# alpha.net
KiCad netlist of a schematic drawn in EAGLE
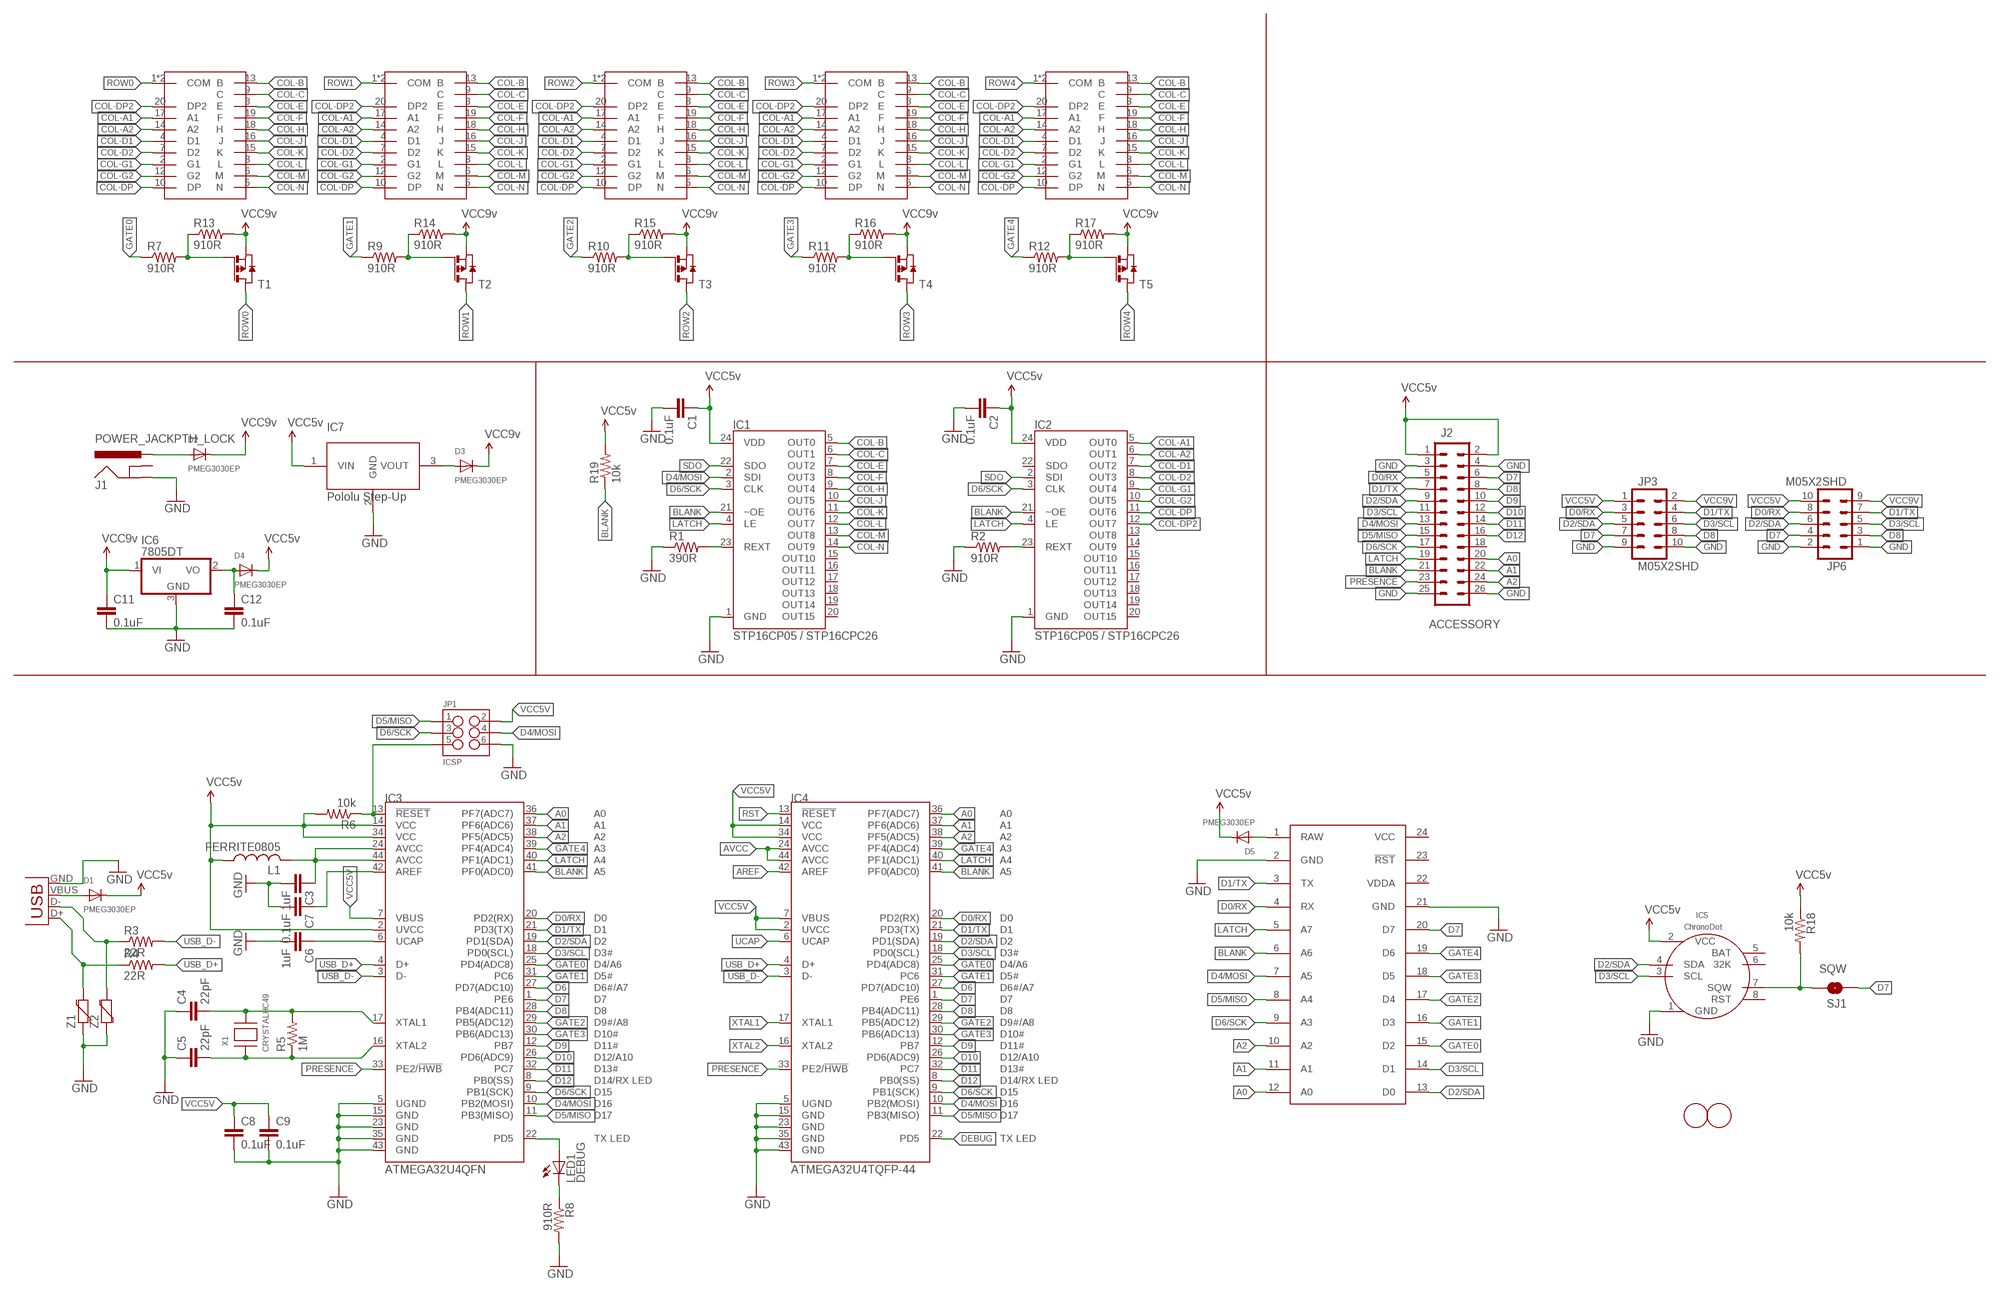
[diagram p0: schematic, sheet 1]

(export (version "E")
  (design (tool "Eeschema 10.0.6"))
  (components
    (comp (ref "C1")
      (value "0.1uF")
      (footprint "eagle-import:0805")
      (fields (field (name "PARTNO") "C0805C104K5RACTU"))
      (libsource (lib "eagle-import") (part "CAP0805"))
    )
    (comp (ref "C2")
      (value "0.1uF")
      (footprint "eagle-import:0805")
      (fields (field (name "PARTNO") "C0805C104K5RACTU"))
      (libsource (lib "eagle-import") (part "CAP0805"))
    )
    (comp (ref "C3")
      (value "1uF")
      (footprint "eagle-import:0805")
      (fields (field (name "PARTNO") "CL21B105KBFNNNE"))
      (libsource (lib "eagle-import") (part "CAP0805"))
    )
    (comp (ref "C4")
      (value "22pF")
      (footprint "eagle-import:0805")
      (fields (field (name "PARTNO") "C0805C220J5GACTU"))
      (libsource (lib "eagle-import") (part "CAP0805"))
    )
    (comp (ref "C5")
      (value "22pF")
      (footprint "eagle-import:0805")
      (fields (field (name "PARTNO") "C0805C220J5GACTU"))
      (libsource (lib "eagle-import") (part "CAP0805"))
    )
    (comp (ref "C6")
      (value "1uF")
      (footprint "eagle-import:0805")
      (fields (field (name "PARTNO") "CL21B105KBFNNNE"))
      (libsource (lib "eagle-import") (part "CAP0805"))
    )
    (comp (ref "C7")
      (value "0.1uF")
      (footprint "eagle-import:0805")
      (fields (field (name "PARTNO") "C0805C104K5RACTU"))
      (libsource (lib "eagle-import") (part "CAP0805"))
    )
    (comp (ref "C8")
      (value "0.1uF")
      (footprint "eagle-import:0805")
      (fields (field (name "PARTNO") "C0805C104K5RACTU"))
      (libsource (lib "eagle-import") (part "CAP0805"))
    )
    (comp (ref "C9")
      (value "0.1uF")
      (footprint "eagle-import:0805")
      (fields (field (name "PARTNO") "C0805C104K5RACTU"))
      (libsource (lib "eagle-import") (part "CAP0805"))
    )
    (comp (ref "C11")
      (value "0.1uF")
      (footprint "eagle-import:0805")
      (fields (field (name "PARTNO") "C0805C104K5RACTU"))
      (libsource (lib "eagle-import") (part "CAP0805"))
    )
    (comp (ref "C12")
      (value "0.1uF")
      (footprint "eagle-import:0805")
      (fields (field (name "PARTNO") "C0805C104K5RACTU"))
      (libsource (lib "eagle-import") (part "CAP0805"))
    )
    (comp (ref "CORE")
      (value "Spark Core")
      (footprint "eagle-import:SPARK_CORE")
      (libsource (lib "eagle-import") (part "SPARK_CORECORE"))
    )
    (comp (ref "D1")
      (value "PMEG3030EP")
      (footprint "eagle-import:SOD-128")
      (fields (field (name "PARTNO") "PMEG3030EP-115"))
      (libsource (lib "eagle-import") (part "DIODESOD-128"))
    )
    (comp (ref "D2")
      (value "PMEG3030EP")
      (footprint "eagle-import:SOD-128")
      (fields (field (name "PARTNO") "PMEG3030EP-115"))
      (libsource (lib "eagle-import") (part "DIODESOD-128"))
    )
    (comp (ref "D3")
      (value "PMEG3030EP")
      (footprint "eagle-import:SOD-128")
      (fields (field (name "PARTNO") "PMEG3030EP-115"))
      (libsource (lib "eagle-import") (part "DIODESOD-128"))
    )
    (comp (ref "D4")
      (value "PMEG3030EP")
      (footprint "eagle-import:SOD-128")
      (fields (field (name "PARTNO") "PMEG3030EP-115"))
      (libsource (lib "eagle-import") (part "DIODESOD-128"))
    )
    (comp (ref "D5")
      (value "PMEG3030EP")
      (footprint "eagle-import:SOD-128")
      (fields (field (name "PARTNO") "PMEG3030EP-115"))
      (libsource (lib "eagle-import") (part "DIODESOD-128"))
    )
    (comp (ref "IC1")
      (value "STP16CP05 / STP16CPC26")
      (footprint "eagle-import:SO-24DW")
      (fields (field (name "PARTNO") "STP16CPC26MTR"))
      (libsource (lib "eagle-import") (part "STP16CP05"))
    )
    (comp (ref "IC2")
      (value "STP16CP05 / STP16CPC26")
      (footprint "eagle-import:SO-24DW")
      (fields (field (name "PARTNO") "STP16CPC26MTR"))
      (libsource (lib "eagle-import") (part "STP16CP05"))
    )
    (comp (ref "IC3")
      (value "ATMEGA32U4QFN")
      (footprint "eagle-import:QFN-44")
      (fields (field (name "PARTNO") "ATMEGA32U4-MUR"))
      (libsource (lib "eagle-import") (part "ATMEGA32U4QFN"))
    )
    (comp (ref "IC4")
      (value "ATMEGA32U4TQFP-44")
      (footprint "eagle-import:TQFP44")
      (fields (field (name "PARTNO") "ATMEGA32U4-AU"))
      (libsource (lib "eagle-import") (part "ATMEGA32U4TQFP-44"))
    )
    (comp (ref "IC5")
      (value "CHRONODOT")
      (footprint "eagle-import:CHRONODOT")
      (libsource (lib "eagle-import") (part "CHRONODOT"))
    )
    (comp (ref "IC6")
      (value "7805DT")
      (footprint "eagle-import:TO252")
      (libsource (lib "eagle-import") (part "78DT05"))
    )
    (comp (ref "IC7")
      (value "Pololu Step-Up")
      (footprint "eagle-import:1X03_LOCK")
      (libsource (lib "eagle-import") (part "POLOLU_REG"))
    )
    (comp (ref "J1")
      (value "POWER_JACKPTH_LOCK")
      (footprint "eagle-import:POWER_JACK_PTH_LOCK")
      (fields (field (name "PARTNO") "PJ-202A"))
      (libsource (lib "eagle-import") (part "POWER_JACKPTH_LOCK"))
    )
    (comp (ref "J2")
      (value "ACCESSORY")
      (footprint "eagle-import:2X13")
      (fields (field (name "PARTNO") "SFH11-PBPC-D13-ST-BK"))
      (libsource (lib "eagle-import") (part "HEADER-M26"))
    )
    (comp (ref "JP1")
      (value "ICSP")
      (footprint "eagle-import:2X3-NS")
      (fields (field (name "PARTNO") "M20-9980346"))
      (libsource (lib "eagle-import") (part "M03X2NO_SILK"))
    )
    (comp (ref "JP2")
      (value "USBSMD")
      (footprint "eagle-import:USB-MINIB")
      (fields (field (name "PARTNO") "690-005-299-043"))
      (libsource (lib "eagle-import") (part "USBSMD"))
    )
    (comp (ref "JP3")
      (value "M05X2SHD")
      (footprint "eagle-import:2X5-SHROUDED")
      (fields (field (name "PARTNO") "302-S101"))
      (libsource (lib "eagle-import") (part "M05X2SHD"))
    )
    (comp (ref "JP6")
      (value "M05X2SHD")
      (footprint "eagle-import:2X5-SHROUDED")
      (fields (field (name "PARTNO") "302-S101"))
      (libsource (lib "eagle-import") (part "M05X2SHD"))
    )
    (comp (ref "L1")
      (value "FERRITE0805")
      (footprint "eagle-import:0805")
      (fields (field (name "PARTNO") "CIM21J601NE"))
      (libsource (lib "eagle-import") (part "FERRITE0805"))
    )
    (comp (ref "LED1")
      (value "DEBUG")
      (footprint "eagle-import:CHIP-LED0805")
      (fields (field (name "PARTNO") "LG R971-KN-1"))
      (libsource (lib "eagle-import") (part "LEDCHIP-LED0805"))
    )
    (comp (ref "R1")
      (value "390R")
      (footprint "eagle-import:0805")
      (fields (field (name "PARTNO") "RC0805FR-07390RL"))
      (libsource (lib "eagle-import") (part "RESISTOR0805-RES"))
    )
    (comp (ref "R2")
      (value "910R")
      (footprint "eagle-import:0805")
      (fields (field (name "PARTNO") "MCR10ERTF9100"))
      (libsource (lib "eagle-import") (part "RESISTOR0805-RES"))
    )
    (comp (ref "R3")
      (value "22R")
      (footprint "eagle-import:0805")
      (fields (field (name "PARTNO") "RC0805FR-0722RL"))
      (libsource (lib "eagle-import") (part "RESISTOR0805-RES"))
    )
    (comp (ref "R4")
      (value "22R")
      (footprint "eagle-import:0805")
      (fields (field (name "PARTNO") "RC0805FR-0722RL"))
      (libsource (lib "eagle-import") (part "RESISTOR0805-RES"))
    )
    (comp (ref "R5")
      (value "1M")
      (footprint "eagle-import:0805")
      (fields (field (name "PARTNO") "RC0805FR-071ML"))
      (libsource (lib "eagle-import") (part "RESISTOR0805-RES"))
    )
    (comp (ref "R6")
      (value "10k")
      (footprint "eagle-import:0805")
      (fields (field (name "PARTNO") "RC0805JR-0710KL"))
      (libsource (lib "eagle-import") (part "RESISTOR0805-RES"))
    )
    (comp (ref "R7")
      (value "910R")
      (footprint "eagle-import:0805")
      (fields (field (name "PARTNO") "MCR10ERTF9100"))
      (libsource (lib "eagle-import") (part "RESISTOR0805-RES"))
    )
    (comp (ref "R8")
      (value "910R")
      (footprint "eagle-import:0805")
      (fields (field (name "PARTNO") "MCR10ERTF9100"))
      (libsource (lib "eagle-import") (part "RESISTOR0805-RES"))
    )
    (comp (ref "R9")
      (value "910R")
      (footprint "eagle-import:0805")
      (fields (field (name "PARTNO") "MCR10ERTF9100"))
      (libsource (lib "eagle-import") (part "RESISTOR0805-RES"))
    )
    (comp (ref "R10")
      (value "910R")
      (footprint "eagle-import:0805")
      (fields (field (name "PARTNO") "MCR10ERTF9100"))
      (libsource (lib "eagle-import") (part "RESISTOR0805-RES"))
    )
    (comp (ref "R11")
      (value "910R")
      (footprint "eagle-import:0805")
      (fields (field (name "PARTNO") "MCR10ERTF9100"))
      (libsource (lib "eagle-import") (part "RESISTOR0805-RES"))
    )
    (comp (ref "R12")
      (value "910R")
      (footprint "eagle-import:0805")
      (fields (field (name "PARTNO") "MCR10ERTF9100"))
      (libsource (lib "eagle-import") (part "RESISTOR0805-RES"))
    )
    (comp (ref "R13")
      (value "910R")
      (footprint "eagle-import:0805")
      (fields (field (name "PARTNO") "MCR10ERTF9100"))
      (libsource (lib "eagle-import") (part "RESISTOR0805-RES"))
    )
    (comp (ref "R14")
      (value "910R")
      (footprint "eagle-import:0805")
      (fields (field (name "PARTNO") "MCR10ERTF9100"))
      (libsource (lib "eagle-import") (part "RESISTOR0805-RES"))
    )
    (comp (ref "R15")
      (value "910R")
      (footprint "eagle-import:0805")
      (fields (field (name "PARTNO") "MCR10ERTF9100"))
      (libsource (lib "eagle-import") (part "RESISTOR0805-RES"))
    )
    (comp (ref "R16")
      (value "910R")
      (footprint "eagle-import:0805")
      (fields (field (name "PARTNO") "MCR10ERTF9100"))
      (libsource (lib "eagle-import") (part "RESISTOR0805-RES"))
    )
    (comp (ref "R17")
      (value "910R")
      (footprint "eagle-import:0805")
      (fields (field (name "PARTNO") "MCR10ERTF9100"))
      (libsource (lib "eagle-import") (part "RESISTOR0805-RES"))
    )
    (comp (ref "R18")
      (value "10k")
      (footprint "eagle-import:0805")
      (fields (field (name "PARTNO") "RC0805JR-0710KL"))
      (libsource (lib "eagle-import") (part "RESISTOR0805-RES"))
    )
    (comp (ref "R19")
      (value "10k")
      (footprint "eagle-import:0805")
      (libsource (lib "eagle-import") (part "RESISTOR0805-RES"))
    )
    (comp (ref "SEG1")
      (value "BL-S230X-12")
      (footprint "eagle-import:BL-S230X-12")
      (libsource (lib "eagle-import") (part "BL-S230X-12"))
    )
    (comp (ref "SEG2")
      (value "BL-S230X-12")
      (footprint "eagle-import:BL-S230X-12")
      (libsource (lib "eagle-import") (part "BL-S230X-12"))
    )
    (comp (ref "SEG3")
      (value "BL-S230X-12")
      (footprint "eagle-import:BL-S230X-12")
      (libsource (lib "eagle-import") (part "BL-S230X-12"))
    )
    (comp (ref "SEG4")
      (value "BL-S230X-12")
      (footprint "eagle-import:BL-S230X-12")
      (libsource (lib "eagle-import") (part "BL-S230X-12"))
    )
    (comp (ref "SEG5")
      (value "BL-S230X-12")
      (footprint "eagle-import:BL-S230X-12")
      (libsource (lib "eagle-import") (part "BL-S230X-12"))
    )
    (comp (ref "SJ1")
      (value "SQW")
      (footprint "eagle-import:SJ_2S-NO")
      (libsource (lib "eagle-import") (part "SOLDERJUMPERNO"))
    )
    (comp (ref "T1")
      (value "PMOSSOT23")
      (footprint "eagle-import:SOT-23")
      (fields (field (name "PARTNO") "FDN352AP"))
      (libsource (lib "eagle-import") (part "PMOSSOT23"))
    )
    (comp (ref "T2")
      (value "PMOSSOT23")
      (footprint "eagle-import:SOT-23")
      (fields (field (name "PARTNO") "FDN352AP"))
      (libsource (lib "eagle-import") (part "PMOSSOT23"))
    )
    (comp (ref "T3")
      (value "PMOSSOT23")
      (footprint "eagle-import:SOT-23")
      (fields (field (name "PARTNO") "FDN352AP"))
      (libsource (lib "eagle-import") (part "PMOSSOT23"))
    )
    (comp (ref "T4")
      (value "PMOSSOT23")
      (footprint "eagle-import:SOT-23")
      (fields (field (name "PARTNO") "FDN352AP"))
      (libsource (lib "eagle-import") (part "PMOSSOT23"))
    )
    (comp (ref "T5")
      (value "PMOSSOT23")
      (footprint "eagle-import:SOT-23")
      (fields (field (name "PARTNO") "FDN352AP"))
      (libsource (lib "eagle-import") (part "PMOSSOT23"))
    )
    (comp (ref "U$1")
      (value "FIDUCIAL")
      (footprint "eagle-import:FIDUCIAL_1MM")
      (libsource (lib "eagle-import") (part "FIDUCIAL"))
    )
    (comp (ref "U$2")
      (value "FIDUCIAL")
      (footprint "eagle-import:FIDUCIAL_1MM")
      (libsource (lib "eagle-import") (part "FIDUCIAL"))
    )
    (comp (ref "X1")
      (value "CRYSTALHC49")
      (footprint "eagle-import:HC49")
      (fields (field (name "PARTNO") "9C-16.000MAAJ-T"))
      (libsource (lib "eagle-import") (part "CRYSTALHC49"))
    )
    (comp (ref "Z1")
      (value "VARISTOR-0603")
      (footprint "eagle-import:0603-RES")
      (fields (field (name "PARTNO") "CG0603MLC-05E"))
      (libsource (lib "eagle-import") (part "VARISTOR-0603"))
    )
    (comp (ref "Z2")
      (value "VARISTOR-0603")
      (footprint "eagle-import:0603-RES")
      (fields (field (name "PARTNO") "CG0603MLC-05E"))
      (libsource (lib "eagle-import") (part "VARISTOR-0603"))
    )
  )
  (nets
    (net (code "1") (name "/VCC") (class "Default")
      (node (ref "CORE") (pin "24") (pinfunction "VCC_24") (pintype "power_in"))
    )
    (net (code "2") (name "/VDDA") (class "Default")
      (node (ref "CORE") (pin "22") (pinfunction "VDDA_22") (pintype "power_in"))
    )
    (net (code "3") (name "A0") (class "Default")
      (node (ref "CORE") (pin "12") (pinfunction "A0_12") (pintype "bidirectional"))
      (node (ref "IC3") (pin "36") (pinfunction "PF7(ADC7)_36") (pintype "bidirectional"))
      (node (ref "IC4") (pin "36") (pinfunction "PF7(ADC7)_36") (pintype "bidirectional"))
      (node (ref "J2") (pin "20") (pinfunction "20_20") (pintype "passive"))
    )
    (net (code "4") (name "A1") (class "Default")
      (node (ref "CORE") (pin "11") (pinfunction "A1_11") (pintype "bidirectional"))
      (node (ref "IC3") (pin "37") (pinfunction "PF6(ADC6)_37") (pintype "bidirectional"))
      (node (ref "IC4") (pin "37") (pinfunction "PF6(ADC6)_37") (pintype "bidirectional"))
      (node (ref "J2") (pin "22") (pinfunction "22_22") (pintype "passive"))
    )
    (net (code "5") (name "A2") (class "Default")
      (node (ref "CORE") (pin "10") (pinfunction "A2_10") (pintype "bidirectional"))
      (node (ref "IC3") (pin "38") (pinfunction "PF5(ADC5)_38") (pintype "bidirectional"))
      (node (ref "IC4") (pin "38") (pinfunction "PF5(ADC5)_38") (pintype "bidirectional"))
      (node (ref "J2") (pin "24") (pinfunction "24_24") (pintype "passive"))
    )
    (net (code "6") (name "AREF") (class "Default")
      (node (ref "C7") (pin "1") (pinfunction "1_1") (pintype "passive"))
      (node (ref "IC3") (pin "42") (pinfunction "AREF_42") (pintype "bidirectional"))
      (node (ref "IC4") (pin "42") (pinfunction "AREF_42") (pintype "bidirectional"))
    )
    (net (code "7") (name "AVCC") (class "Default")
      (node (ref "C3") (pin "1") (pinfunction "1_1") (pintype "passive"))
      (node (ref "IC3") (pin "24") (pinfunction "AVCC_24") (pintype "bidirectional"))
      (node (ref "IC3") (pin "44") (pinfunction "AVCC_44") (pintype "bidirectional"))
      (node (ref "IC4") (pin "24") (pinfunction "AVCC_24") (pintype "bidirectional"))
      (node (ref "IC4") (pin "44") (pinfunction "AVCC_44") (pintype "bidirectional"))
      (node (ref "L1") (pin "2") (pinfunction "2_2") (pintype "passive"))
    )
    (net (code "8") (name "BLANK") (class "Default")
      (node (ref "CORE") (pin "6") (pinfunction "A6_6") (pintype "bidirectional"))
      (node (ref "IC1") (pin "21") (pinfunction "~{OE}_21") (pintype "bidirectional"))
      (node (ref "IC2") (pin "21") (pinfunction "~{OE}_21") (pintype "bidirectional"))
      (node (ref "IC3") (pin "41") (pinfunction "PF0(ADC0)_41") (pintype "bidirectional"))
      (node (ref "IC4") (pin "41") (pinfunction "PF0(ADC0)_41") (pintype "bidirectional"))
      (node (ref "J2") (pin "21") (pinfunction "21_21") (pintype "passive"))
      (node (ref "R19") (pin "1") (pinfunction "1_1") (pintype "passive"))
    )
    (net (code "9") (name "COL-A1") (class "Default")
      (node (ref "IC2") (pin "5") (pinfunction "OUT0_5") (pintype "bidirectional"))
      (node (ref "SEG1") (pin "17") (pinfunction "A1_17") (pintype "bidirectional"))
      (node (ref "SEG2") (pin "17") (pinfunction "A1_17") (pintype "bidirectional"))
      (node (ref "SEG3") (pin "17") (pinfunction "A1_17") (pintype "bidirectional"))
      (node (ref "SEG4") (pin "17") (pinfunction "A1_17") (pintype "bidirectional"))
      (node (ref "SEG5") (pin "17") (pinfunction "A1_17") (pintype "bidirectional"))
    )
    (net (code "10") (name "COL-A2") (class "Default")
      (node (ref "IC2") (pin "6") (pinfunction "OUT1_6") (pintype "bidirectional"))
      (node (ref "SEG1") (pin "14") (pinfunction "A2_14") (pintype "bidirectional"))
      (node (ref "SEG2") (pin "14") (pinfunction "A2_14") (pintype "bidirectional"))
      (node (ref "SEG3") (pin "14") (pinfunction "A2_14") (pintype "bidirectional"))
      (node (ref "SEG4") (pin "14") (pinfunction "A2_14") (pintype "bidirectional"))
      (node (ref "SEG5") (pin "14") (pinfunction "A2_14") (pintype "bidirectional"))
    )
    (net (code "11") (name "COL-B") (class "Default")
      (node (ref "IC1") (pin "5") (pinfunction "OUT0_5") (pintype "bidirectional"))
      (node (ref "SEG1") (pin "13") (pinfunction "B_13") (pintype "bidirectional"))
      (node (ref "SEG2") (pin "13") (pinfunction "B_13") (pintype "bidirectional"))
      (node (ref "SEG3") (pin "13") (pinfunction "B_13") (pintype "bidirectional"))
      (node (ref "SEG4") (pin "13") (pinfunction "B_13") (pintype "bidirectional"))
      (node (ref "SEG5") (pin "13") (pinfunction "B_13") (pintype "bidirectional"))
    )
    (net (code "12") (name "COL-C") (class "Default")
      (node (ref "IC1") (pin "6") (pinfunction "OUT1_6") (pintype "bidirectional"))
      (node (ref "SEG1") (pin "9") (pinfunction "C_9") (pintype "bidirectional"))
      (node (ref "SEG2") (pin "9") (pinfunction "C_9") (pintype "bidirectional"))
      (node (ref "SEG3") (pin "9") (pinfunction "C_9") (pintype "bidirectional"))
      (node (ref "SEG4") (pin "9") (pinfunction "C_9") (pintype "bidirectional"))
      (node (ref "SEG5") (pin "9") (pinfunction "C_9") (pintype "bidirectional"))
    )
    (net (code "13") (name "COL-D1") (class "Default")
      (node (ref "IC2") (pin "7") (pinfunction "OUT2_7") (pintype "bidirectional"))
      (node (ref "SEG1") (pin "4") (pinfunction "D1_4") (pintype "bidirectional"))
      (node (ref "SEG2") (pin "4") (pinfunction "D1_4") (pintype "bidirectional"))
      (node (ref "SEG3") (pin "4") (pinfunction "D1_4") (pintype "bidirectional"))
      (node (ref "SEG4") (pin "4") (pinfunction "D1_4") (pintype "bidirectional"))
      (node (ref "SEG5") (pin "4") (pinfunction "D1_4") (pintype "bidirectional"))
    )
    (net (code "14") (name "COL-D2") (class "Default")
      (node (ref "IC2") (pin "8") (pinfunction "OUT3_8") (pintype "bidirectional"))
      (node (ref "SEG1") (pin "7") (pinfunction "D2_7") (pintype "bidirectional"))
      (node (ref "SEG2") (pin "7") (pinfunction "D2_7") (pintype "bidirectional"))
      (node (ref "SEG3") (pin "7") (pinfunction "D2_7") (pintype "bidirectional"))
      (node (ref "SEG4") (pin "7") (pinfunction "D2_7") (pintype "bidirectional"))
      (node (ref "SEG5") (pin "7") (pinfunction "D2_7") (pintype "bidirectional"))
    )
    (net (code "15") (name "COL-DP") (class "Default")
      (node (ref "IC2") (pin "11") (pinfunction "OUT6_11") (pintype "bidirectional"))
      (node (ref "SEG1") (pin "10") (pinfunction "DP_10") (pintype "bidirectional"))
      (node (ref "SEG2") (pin "10") (pinfunction "DP_10") (pintype "bidirectional"))
      (node (ref "SEG3") (pin "10") (pinfunction "DP_10") (pintype "bidirectional"))
      (node (ref "SEG4") (pin "10") (pinfunction "DP_10") (pintype "bidirectional"))
      (node (ref "SEG5") (pin "10") (pinfunction "DP_10") (pintype "bidirectional"))
    )
    (net (code "16") (name "COL-DP2") (class "Default")
      (node (ref "IC2") (pin "12") (pinfunction "OUT7_12") (pintype "bidirectional"))
      (node (ref "SEG1") (pin "20") (pinfunction "DP2_20") (pintype "bidirectional"))
      (node (ref "SEG2") (pin "20") (pinfunction "DP2_20") (pintype "bidirectional"))
      (node (ref "SEG3") (pin "20") (pinfunction "DP2_20") (pintype "bidirectional"))
      (node (ref "SEG4") (pin "20") (pinfunction "DP2_20") (pintype "bidirectional"))
      (node (ref "SEG5") (pin "20") (pinfunction "DP2_20") (pintype "bidirectional"))
    )
    (net (code "17") (name "COL-E") (class "Default")
      (node (ref "IC1") (pin "7") (pinfunction "OUT2_7") (pintype "bidirectional"))
      (node (ref "SEG1") (pin "3") (pinfunction "E_3") (pintype "bidirectional"))
      (node (ref "SEG2") (pin "3") (pinfunction "E_3") (pintype "bidirectional"))
      (node (ref "SEG3") (pin "3") (pinfunction "E_3") (pintype "bidirectional"))
      (node (ref "SEG4") (pin "3") (pinfunction "E_3") (pintype "bidirectional"))
      (node (ref "SEG5") (pin "3") (pinfunction "E_3") (pintype "bidirectional"))
    )
    (net (code "18") (name "COL-F") (class "Default")
      (node (ref "IC1") (pin "8") (pinfunction "OUT3_8") (pintype "bidirectional"))
      (node (ref "SEG1") (pin "19") (pinfunction "F_19") (pintype "bidirectional"))
      (node (ref "SEG2") (pin "19") (pinfunction "F_19") (pintype "bidirectional"))
      (node (ref "SEG3") (pin "19") (pinfunction "F_19") (pintype "bidirectional"))
      (node (ref "SEG4") (pin "19") (pinfunction "F_19") (pintype "bidirectional"))
      (node (ref "SEG5") (pin "19") (pinfunction "F_19") (pintype "bidirectional"))
    )
    (net (code "19") (name "COL-G1") (class "Default")
      (node (ref "IC2") (pin "9") (pinfunction "OUT4_9") (pintype "bidirectional"))
      (node (ref "SEG1") (pin "2") (pinfunction "G1_2") (pintype "bidirectional"))
      (node (ref "SEG2") (pin "2") (pinfunction "G1_2") (pintype "bidirectional"))
      (node (ref "SEG3") (pin "2") (pinfunction "G1_2") (pintype "bidirectional"))
      (node (ref "SEG4") (pin "2") (pinfunction "G1_2") (pintype "bidirectional"))
      (node (ref "SEG5") (pin "2") (pinfunction "G1_2") (pintype "bidirectional"))
    )
    (net (code "20") (name "COL-G2") (class "Default")
      (node (ref "IC2") (pin "10") (pinfunction "OUT5_10") (pintype "bidirectional"))
      (node (ref "SEG1") (pin "12") (pinfunction "G2_12") (pintype "bidirectional"))
      (node (ref "SEG2") (pin "12") (pinfunction "G2_12") (pintype "bidirectional"))
      (node (ref "SEG3") (pin "12") (pinfunction "G2_12") (pintype "bidirectional"))
      (node (ref "SEG4") (pin "12") (pinfunction "G2_12") (pintype "bidirectional"))
      (node (ref "SEG5") (pin "12") (pinfunction "G2_12") (pintype "bidirectional"))
    )
    (net (code "21") (name "COL-H") (class "Default")
      (node (ref "IC1") (pin "9") (pinfunction "OUT4_9") (pintype "bidirectional"))
      (node (ref "SEG1") (pin "18") (pinfunction "H_18") (pintype "bidirectional"))
      (node (ref "SEG2") (pin "18") (pinfunction "H_18") (pintype "bidirectional"))
      (node (ref "SEG3") (pin "18") (pinfunction "H_18") (pintype "bidirectional"))
      (node (ref "SEG4") (pin "18") (pinfunction "H_18") (pintype "bidirectional"))
      (node (ref "SEG5") (pin "18") (pinfunction "H_18") (pintype "bidirectional"))
    )
    (net (code "22") (name "COL-J") (class "Default")
      (node (ref "IC1") (pin "10") (pinfunction "OUT5_10") (pintype "bidirectional"))
      (node (ref "SEG1") (pin "16") (pinfunction "J_16") (pintype "bidirectional"))
      (node (ref "SEG2") (pin "16") (pinfunction "J_16") (pintype "bidirectional"))
      (node (ref "SEG3") (pin "16") (pinfunction "J_16") (pintype "bidirectional"))
      (node (ref "SEG4") (pin "16") (pinfunction "J_16") (pintype "bidirectional"))
      (node (ref "SEG5") (pin "16") (pinfunction "J_16") (pintype "bidirectional"))
    )
    (net (code "23") (name "COL-K") (class "Default")
      (node (ref "IC1") (pin "11") (pinfunction "OUT6_11") (pintype "bidirectional"))
      (node (ref "SEG1") (pin "15") (pinfunction "K_15") (pintype "bidirectional"))
      (node (ref "SEG2") (pin "15") (pinfunction "K_15") (pintype "bidirectional"))
      (node (ref "SEG3") (pin "15") (pinfunction "K_15") (pintype "bidirectional"))
      (node (ref "SEG4") (pin "15") (pinfunction "K_15") (pintype "bidirectional"))
      (node (ref "SEG5") (pin "15") (pinfunction "K_15") (pintype "bidirectional"))
    )
    (net (code "24") (name "COL-L") (class "Default")
      (node (ref "IC1") (pin "12") (pinfunction "OUT7_12") (pintype "bidirectional"))
      (node (ref "SEG1") (pin "8") (pinfunction "L_8") (pintype "bidirectional"))
      (node (ref "SEG2") (pin "8") (pinfunction "L_8") (pintype "bidirectional"))
      (node (ref "SEG3") (pin "8") (pinfunction "L_8") (pintype "bidirectional"))
      (node (ref "SEG4") (pin "8") (pinfunction "L_8") (pintype "bidirectional"))
      (node (ref "SEG5") (pin "8") (pinfunction "L_8") (pintype "bidirectional"))
    )
    (net (code "25") (name "COL-M") (class "Default")
      (node (ref "IC1") (pin "13") (pinfunction "OUT8_13") (pintype "bidirectional"))
      (node (ref "SEG1") (pin "6") (pinfunction "M_6") (pintype "bidirectional"))
      (node (ref "SEG2") (pin "6") (pinfunction "M_6") (pintype "bidirectional"))
      (node (ref "SEG3") (pin "6") (pinfunction "M_6") (pintype "bidirectional"))
      (node (ref "SEG4") (pin "6") (pinfunction "M_6") (pintype "bidirectional"))
      (node (ref "SEG5") (pin "6") (pinfunction "M_6") (pintype "bidirectional"))
    )
    (net (code "26") (name "COL-N") (class "Default")
      (node (ref "IC1") (pin "14") (pinfunction "OUT9_14") (pintype "bidirectional"))
      (node (ref "SEG1") (pin "5") (pinfunction "N_5") (pintype "bidirectional"))
      (node (ref "SEG2") (pin "5") (pinfunction "N_5") (pintype "bidirectional"))
      (node (ref "SEG3") (pin "5") (pinfunction "N_5") (pintype "bidirectional"))
      (node (ref "SEG4") (pin "5") (pinfunction "N_5") (pintype "bidirectional"))
      (node (ref "SEG5") (pin "5") (pinfunction "N_5") (pintype "bidirectional"))
    )
    (net (code "27") (name "D0{slash}RX") (class "Default")
      (node (ref "CORE") (pin "4") (pinfunction "RX_4") (pintype "bidirectional"))
      (node (ref "IC3") (pin "20") (pinfunction "PD2(RX)_20") (pintype "bidirectional"))
      (node (ref "IC4") (pin "20") (pinfunction "PD2(RX)_20") (pintype "bidirectional"))
      (node (ref "J2") (pin "5") (pinfunction "5_5") (pintype "passive"))
      (node (ref "JP3") (pin "3") (pinfunction "3_3") (pintype "passive"))
      (node (ref "JP6") (pin "8") (pinfunction "8_8") (pintype "passive"))
    )
    (net (code "28") (name "D1{slash}TX") (class "Default")
      (node (ref "CORE") (pin "3") (pinfunction "TX_3") (pintype "bidirectional"))
      (node (ref "IC3") (pin "21") (pinfunction "PD3(TX)_21") (pintype "bidirectional"))
      (node (ref "IC4") (pin "21") (pinfunction "PD3(TX)_21") (pintype "bidirectional"))
      (node (ref "J2") (pin "7") (pinfunction "7_7") (pintype "passive"))
      (node (ref "JP3") (pin "4") (pinfunction "4_4") (pintype "passive"))
      (node (ref "JP6") (pin "7") (pinfunction "7_7") (pintype "passive"))
    )
    (net (code "29") (name "D2{slash}SDA") (class "Default")
      (node (ref "CORE") (pin "13") (pinfunction "D0_13") (pintype "bidirectional"))
      (node (ref "IC3") (pin "19") (pinfunction "PD1(SDA)_19") (pintype "bidirectional"))
      (node (ref "IC4") (pin "19") (pinfunction "PD1(SDA)_19") (pintype "bidirectional"))
      (node (ref "IC5") (pin "4") (pinfunction "SDA_4") (pintype "bidirectional"))
      (node (ref "J2") (pin "9") (pinfunction "9_9") (pintype "passive"))
      (node (ref "JP3") (pin "5") (pinfunction "5_5") (pintype "passive"))
      (node (ref "JP6") (pin "6") (pinfunction "6_6") (pintype "passive"))
    )
    (net (code "30") (name "D3{slash}SCL") (class "Default")
      (node (ref "CORE") (pin "14") (pinfunction "D1_14") (pintype "bidirectional"))
      (node (ref "IC3") (pin "18") (pinfunction "PD0(SCL)_18") (pintype "bidirectional"))
      (node (ref "IC4") (pin "18") (pinfunction "PD0(SCL)_18") (pintype "bidirectional"))
      (node (ref "IC5") (pin "3") (pinfunction "SCL_3") (pintype "bidirectional"))
      (node (ref "J2") (pin "11") (pinfunction "11_11") (pintype "passive"))
      (node (ref "JP3") (pin "6") (pinfunction "6_6") (pintype "passive"))
      (node (ref "JP6") (pin "5") (pinfunction "5_5") (pintype "passive"))
    )
    (net (code "31") (name "D4{slash}MOSI") (class "Default")
      (node (ref "CORE") (pin "7") (pinfunction "A5_7") (pintype "bidirectional"))
      (node (ref "IC1") (pin "2") (pinfunction "SDI_2") (pintype "bidirectional"))
      (node (ref "IC3") (pin "10") (pinfunction "PB2(MOSI)_10") (pintype "bidirectional"))
      (node (ref "IC4") (pin "10") (pinfunction "PB2(MOSI)_10") (pintype "bidirectional"))
      (node (ref "J2") (pin "13") (pinfunction "13_13") (pintype "passive"))
      (node (ref "JP1") (pin "4") (pinfunction "4_4") (pintype "bidirectional"))
    )
    (net (code "32") (name "D5{slash}MISO") (class "Default")
      (node (ref "CORE") (pin "8") (pinfunction "A4_8") (pintype "bidirectional"))
      (node (ref "IC3") (pin "11") (pinfunction "PB3(MISO)_11") (pintype "bidirectional"))
      (node (ref "IC4") (pin "11") (pinfunction "PB3(MISO)_11") (pintype "bidirectional"))
      (node (ref "J2") (pin "15") (pinfunction "15_15") (pintype "passive"))
      (node (ref "JP1") (pin "1") (pinfunction "1_1") (pintype "bidirectional"))
    )
    (net (code "33") (name "D6") (class "Default")
      (node (ref "IC3") (pin "27") (pinfunction "PD7(ADC10)_27") (pintype "bidirectional"))
      (node (ref "IC4") (pin "27") (pinfunction "PD7(ADC10)_27") (pintype "bidirectional"))
    )
    (net (code "34") (name "D6{slash}SCK") (class "Default")
      (node (ref "CORE") (pin "9") (pinfunction "A3_9") (pintype "bidirectional"))
      (node (ref "IC1") (pin "3") (pinfunction "CLK_3") (pintype "bidirectional"))
      (node (ref "IC2") (pin "3") (pinfunction "CLK_3") (pintype "bidirectional"))
      (node (ref "IC3") (pin "9") (pinfunction "PB1(SCK)_9") (pintype "bidirectional"))
      (node (ref "IC4") (pin "9") (pinfunction "PB1(SCK)_9") (pintype "bidirectional"))
      (node (ref "J2") (pin "17") (pinfunction "17_17") (pintype "passive"))
      (node (ref "JP1") (pin "3") (pinfunction "3_3") (pintype "bidirectional"))
    )
    (net (code "35") (name "D7") (class "Default")
      (node (ref "CORE") (pin "20") (pinfunction "D7_20") (pintype "bidirectional"))
      (node (ref "IC3") (pin "1") (pinfunction "PE6_1") (pintype "bidirectional"))
      (node (ref "IC4") (pin "1") (pinfunction "PE6_1") (pintype "bidirectional"))
      (node (ref "J2") (pin "6") (pinfunction "6_6") (pintype "passive"))
      (node (ref "JP3") (pin "7") (pinfunction "7_7") (pintype "passive"))
      (node (ref "JP6") (pin "4") (pinfunction "4_4") (pintype "passive"))
      (node (ref "SJ1") (pin "1") (pinfunction "1_1") (pintype "passive"))
    )
    (net (code "36") (name "D8") (class "Default")
      (node (ref "IC3") (pin "28") (pinfunction "PB4(ADC11)_28") (pintype "bidirectional"))
      (node (ref "IC4") (pin "28") (pinfunction "PB4(ADC11)_28") (pintype "bidirectional"))
      (node (ref "J2") (pin "8") (pinfunction "8_8") (pintype "passive"))
      (node (ref "JP3") (pin "8") (pinfunction "8_8") (pintype "passive"))
      (node (ref "JP6") (pin "3") (pinfunction "3_3") (pintype "passive"))
    )
    (net (code "37") (name "D9") (class "Default")
      (node (ref "IC3") (pin "12") (pinfunction "PB7_12") (pintype "bidirectional"))
      (node (ref "IC4") (pin "12") (pinfunction "PB7_12") (pintype "bidirectional"))
      (node (ref "J2") (pin "10") (pinfunction "10_10") (pintype "passive"))
    )
    (net (code "38") (name "D10") (class "Default")
      (node (ref "IC3") (pin "26") (pinfunction "PD6(ADC9)_26") (pintype "bidirectional"))
      (node (ref "IC4") (pin "26") (pinfunction "PD6(ADC9)_26") (pintype "bidirectional"))
      (node (ref "J2") (pin "12") (pinfunction "12_12") (pintype "passive"))
    )
    (net (code "39") (name "D11") (class "Default")
      (node (ref "IC3") (pin "32") (pinfunction "PC7_32") (pintype "bidirectional"))
      (node (ref "IC4") (pin "32") (pinfunction "PC7_32") (pintype "bidirectional"))
      (node (ref "J2") (pin "14") (pinfunction "14_14") (pintype "passive"))
    )
    (net (code "40") (name "D12") (class "Default")
      (node (ref "IC3") (pin "8") (pinfunction "PB0(SS)_8") (pintype "bidirectional"))
      (node (ref "IC4") (pin "8") (pinfunction "PB0(SS)_8") (pintype "bidirectional"))
      (node (ref "J2") (pin "16") (pinfunction "16_16") (pintype "passive"))
    )
    (net (code "41") (name "DEBUG") (class "Default")
      (node (ref "IC3") (pin "22") (pinfunction "PD5_22") (pintype "bidirectional"))
      (node (ref "IC4") (pin "22") (pinfunction "PD5_22") (pintype "bidirectional"))
      (node (ref "LED1") (pin "A") (pinfunction "A_A") (pintype "passive"))
    )
    (net (code "42") (name "GATE0") (class "Default")
      (node (ref "CORE") (pin "15") (pinfunction "D2_15") (pintype "bidirectional"))
      (node (ref "IC3") (pin "25") (pinfunction "PD4(ADC8)_25") (pintype "bidirectional"))
      (node (ref "IC4") (pin "25") (pinfunction "PD4(ADC8)_25") (pintype "bidirectional"))
      (node (ref "R7") (pin "1") (pinfunction "1_1") (pintype "passive"))
    )
    (net (code "43") (name "GATE1") (class "Default")
      (node (ref "CORE") (pin "16") (pinfunction "D3_16") (pintype "bidirectional"))
      (node (ref "IC3") (pin "31") (pinfunction "PC6_31") (pintype "bidirectional"))
      (node (ref "IC4") (pin "31") (pinfunction "PC6_31") (pintype "bidirectional"))
      (node (ref "R9") (pin "1") (pinfunction "1_1") (pintype "passive"))
    )
    (net (code "44") (name "GATE2") (class "Default")
      (node (ref "CORE") (pin "17") (pinfunction "D4_17") (pintype "bidirectional"))
      (node (ref "IC3") (pin "29") (pinfunction "PB5(ADC12)_29") (pintype "bidirectional"))
      (node (ref "IC4") (pin "29") (pinfunction "PB5(ADC12)_29") (pintype "bidirectional"))
      (node (ref "R10") (pin "1") (pinfunction "1_1") (pintype "passive"))
    )
    (net (code "45") (name "GATE3") (class "Default")
      (node (ref "CORE") (pin "18") (pinfunction "D5_18") (pintype "bidirectional"))
      (node (ref "IC3") (pin "30") (pinfunction "PB6(ADC13)_30") (pintype "bidirectional"))
      (node (ref "IC4") (pin "30") (pinfunction "PB6(ADC13)_30") (pintype "bidirectional"))
      (node (ref "R11") (pin "1") (pinfunction "1_1") (pintype "passive"))
    )
    (net (code "46") (name "GATE4") (class "Default")
      (node (ref "CORE") (pin "19") (pinfunction "D6_19") (pintype "bidirectional"))
      (node (ref "IC3") (pin "39") (pinfunction "PF4(ADC4)_39") (pintype "bidirectional"))
      (node (ref "IC4") (pin "39") (pinfunction "PF4(ADC4)_39") (pintype "bidirectional"))
      (node (ref "R12") (pin "1") (pinfunction "1_1") (pintype "passive"))
    )
    (net (code "47") (name "GND") (class "Default")
      (node (ref "C1") (pin "2") (pinfunction "2_2") (pintype "passive"))
      (node (ref "C11") (pin "2") (pinfunction "2_2") (pintype "passive"))
      (node (ref "C12") (pin "2") (pinfunction "2_2") (pintype "passive"))
      (node (ref "C2") (pin "2") (pinfunction "2_2") (pintype "passive"))
      (node (ref "C3") (pin "2") (pinfunction "2_2") (pintype "passive"))
      (node (ref "C4") (pin "1") (pinfunction "1_1") (pintype "passive"))
      (node (ref "C5") (pin "1") (pinfunction "1_1") (pintype "passive"))
      (node (ref "C6") (pin "2") (pinfunction "2_2") (pintype "passive"))
      (node (ref "C7") (pin "2") (pinfunction "2_2") (pintype "passive"))
      (node (ref "C8") (pin "2") (pinfunction "2_2") (pintype "passive"))
      (node (ref "C9") (pin "2") (pinfunction "2_2") (pintype "passive"))
      (node (ref "CORE") (pin "2") (pinfunction "GND_2") (pintype "power_in"))
      (node (ref "CORE") (pin "21") (pinfunction "GND_21") (pintype "power_in"))
      (node (ref "IC1") (pin "1") (pinfunction "GND_1") (pintype "bidirectional"))
      (node (ref "IC2") (pin "1") (pinfunction "GND_1") (pintype "bidirectional"))
      (node (ref "IC3") (pin "15") (pinfunction "GND_15") (pintype "bidirectional"))
      (node (ref "IC3") (pin "23") (pinfunction "GND_23") (pintype "bidirectional"))
      (node (ref "IC3") (pin "35") (pinfunction "GND_35") (pintype "bidirectional"))
      (node (ref "IC3") (pin "43") (pinfunction "GND_43") (pintype "bidirectional"))
      (node (ref "IC3") (pin "5") (pinfunction "UGND_5") (pintype "bidirectional"))
      (node (ref "IC4") (pin "15") (pinfunction "GND_15") (pintype "bidirectional"))
      (node (ref "IC4") (pin "23") (pinfunction "GND_23") (pintype "bidirectional"))
      (node (ref "IC4") (pin "35") (pinfunction "GND_35") (pintype "bidirectional"))
      (node (ref "IC4") (pin "43") (pinfunction "GND_43") (pintype "bidirectional"))
      (node (ref "IC4") (pin "5") (pinfunction "UGND_5") (pintype "bidirectional"))
      (node (ref "IC5") (pin "1") (pinfunction "GND_1") (pintype "bidirectional"))
      (node (ref "IC6") (pin "3") (pinfunction "GND_3") (pintype "passive"))
      (node (ref "IC7") (pin "2") (pinfunction "GND_2") (pintype "bidirectional"))
      (node (ref "J1") (pin "GND") (pinfunction "GND_GND") (pintype "bidirectional"))
      (node (ref "J2") (pin "25") (pinfunction "25_25") (pintype "passive"))
      (node (ref "J2") (pin "26") (pinfunction "26_26") (pintype "passive"))
      (node (ref "J2") (pin "3") (pinfunction "3_3") (pintype "passive"))
      (node (ref "J2") (pin "4") (pinfunction "4_4") (pintype "passive"))
      (node (ref "JP1") (pin "6") (pinfunction "6_6") (pintype "bidirectional"))
      (node (ref "JP2") (pin "GND") (pinfunction "GND_GND") (pintype "bidirectional"))
      (node (ref "JP3") (pin "10") (pinfunction "10_10") (pintype "passive"))
      (node (ref "JP3") (pin "9") (pinfunction "9_9") (pintype "passive"))
      (node (ref "JP6") (pin "1") (pinfunction "1_1") (pintype "passive"))
      (node (ref "JP6") (pin "2") (pinfunction "2_2") (pintype "passive"))
      (node (ref "R1") (pin "1") (pinfunction "1_1") (pintype "passive"))
      (node (ref "R2") (pin "1") (pinfunction "1_1") (pintype "passive"))
      (node (ref "R8") (pin "2") (pinfunction "2_2") (pintype "passive"))
      (node (ref "Z1") (pin "1") (pinfunction "1_1") (pintype "passive"))
      (node (ref "Z2") (pin "1") (pinfunction "1_1") (pintype "passive"))
    )
    (net (code "48") (name "LATCH") (class "Default")
      (node (ref "CORE") (pin "5") (pinfunction "A7_5") (pintype "bidirectional"))
      (node (ref "IC1") (pin "4") (pinfunction "LE_4") (pintype "bidirectional"))
      (node (ref "IC2") (pin "4") (pinfunction "LE_4") (pintype "bidirectional"))
      (node (ref "IC3") (pin "40") (pinfunction "PF1(ADC1)_40") (pintype "bidirectional"))
      (node (ref "IC4") (pin "40") (pinfunction "PF1(ADC1)_40") (pintype "bidirectional"))
      (node (ref "J2") (pin "19") (pinfunction "19_19") (pintype "passive"))
    )
    (net (code "49") (name "Net-(CORE-RAW)") (class "Default")
      (node (ref "CORE") (pin "1") (pinfunction "RAW_1") (pintype "power_in"))
      (node (ref "D5") (pin "A") (pinfunction "A_A") (pintype "passive"))
    )
    (net (code "50") (name "Net-(D1-PadA)") (class "Default")
      (node (ref "D1") (pin "A") (pinfunction "A_A") (pintype "passive"))
      (node (ref "JP2") (pin "VBUS") (pinfunction "VBUS_VBUS") (pintype "bidirectional"))
    )
    (net (code "51") (name "Net-(D2-PadA)") (class "Default")
      (node (ref "D2") (pin "A") (pinfunction "A_A") (pintype "passive"))
      (node (ref "J1") (pin "PWR") (pinfunction "PWR_PWR") (pintype "bidirectional"))
    )
    (net (code "52") (name "Net-(IC1-REXT)") (class "Default")
      (node (ref "IC1") (pin "23") (pinfunction "REXT_23") (pintype "bidirectional"))
      (node (ref "R1") (pin "2") (pinfunction "2_2") (pintype "passive"))
    )
    (net (code "53") (name "Net-(IC2-REXT)") (class "Default")
      (node (ref "IC2") (pin "23") (pinfunction "REXT_23") (pintype "bidirectional"))
      (node (ref "R2") (pin "2") (pinfunction "2_2") (pintype "passive"))
    )
    (net (code "54") (name "Net-(IC5-SQW)") (class "Default")
      (node (ref "IC5") (pin "7") (pinfunction "SQW_7") (pintype "bidirectional"))
      (node (ref "R18") (pin "2") (pinfunction "2_2") (pintype "passive"))
      (node (ref "SJ1") (pin "2") (pinfunction "2_2") (pintype "passive"))
    )
    (net (code "55") (name "Net-(IC6-VO)") (class "Default")
      (node (ref "C12") (pin "1") (pinfunction "1_1") (pintype "passive"))
      (node (ref "D4") (pin "A") (pinfunction "A_A") (pintype "passive"))
      (node (ref "IC6") (pin "2") (pinfunction "VO_2") (pintype "passive"))
    )
    (net (code "56") (name "Net-(IC7-VOUT)") (class "Default")
      (node (ref "D3") (pin "A") (pinfunction "A_A") (pintype "passive"))
      (node (ref "IC7") (pin "3") (pinfunction "VOUT_3") (pintype "bidirectional"))
    )
    (net (code "57") (name "Net-(JP2-PadD+)") (class "Default")
      (node (ref "JP2") (pin "D+") (pinfunction "D+_D+") (pintype "bidirectional"))
      (node (ref "R4") (pin "1") (pinfunction "1_1") (pintype "passive"))
      (node (ref "Z1") (pin "2") (pinfunction "2_2") (pintype "passive"))
    )
    (net (code "58") (name "Net-(JP2-PadD-)") (class "Default")
      (node (ref "JP2") (pin "D-") (pinfunction "D-_D-") (pintype "bidirectional"))
      (node (ref "R3") (pin "1") (pinfunction "1_1") (pintype "passive"))
      (node (ref "Z2") (pin "2") (pinfunction "2_2") (pintype "passive"))
    )
    (net (code "59") (name "Net-(LED1-PadC)") (class "Default")
      (node (ref "LED1") (pin "C") (pinfunction "C_C") (pintype "passive"))
      (node (ref "R8") (pin "1") (pinfunction "1_1") (pintype "passive"))
    )
    (net (code "60") (name "Net-(T1-G)") (class "Default")
      (node (ref "R13") (pin "1") (pinfunction "1_1") (pintype "passive"))
      (node (ref "R7") (pin "2") (pinfunction "2_2") (pintype "passive"))
      (node (ref "T1") (pin "3") (pinfunction "G_3") (pintype "passive"))
    )
    (net (code "61") (name "Net-(T2-G)") (class "Default")
      (node (ref "R14") (pin "1") (pinfunction "1_1") (pintype "passive"))
      (node (ref "R9") (pin "2") (pinfunction "2_2") (pintype "passive"))
      (node (ref "T2") (pin "3") (pinfunction "G_3") (pintype "passive"))
    )
    (net (code "62") (name "Net-(T3-G)") (class "Default")
      (node (ref "R10") (pin "2") (pinfunction "2_2") (pintype "passive"))
      (node (ref "R15") (pin "1") (pinfunction "1_1") (pintype "passive"))
      (node (ref "T3") (pin "3") (pinfunction "G_3") (pintype "passive"))
    )
    (net (code "63") (name "Net-(T4-G)") (class "Default")
      (node (ref "R11") (pin "2") (pinfunction "2_2") (pintype "passive"))
      (node (ref "R16") (pin "1") (pinfunction "1_1") (pintype "passive"))
      (node (ref "T4") (pin "3") (pinfunction "G_3") (pintype "passive"))
    )
    (net (code "64") (name "Net-(T5-G)") (class "Default")
      (node (ref "R12") (pin "2") (pinfunction "2_2") (pintype "passive"))
      (node (ref "R17") (pin "1") (pinfunction "1_1") (pintype "passive"))
      (node (ref "T5") (pin "3") (pinfunction "G_3") (pintype "passive"))
    )
    (net (code "65") (name "PRESENCE") (class "Default")
      (node (ref "IC3") (pin "33") (pinfunction "PE2/~{HWB}_33") (pintype "bidirectional"))
      (node (ref "IC4") (pin "33") (pinfunction "PE2/~{HWB}_33") (pintype "bidirectional"))
      (node (ref "J2") (pin "23") (pinfunction "23_23") (pintype "passive"))
    )
    (net (code "66") (name "ROW0") (class "Default")
      (node (ref "SEG1") (pin "1") (pinfunction "COM_1") (pintype "bidirectional"))
      (node (ref "SEG1") (pin "11") (pinfunction "COM_11") (pintype "bidirectional"))
      (node (ref "T1") (pin "1") (pinfunction "D_1") (pintype "passive"))
    )
    (net (code "67") (name "ROW1") (class "Default")
      (node (ref "SEG2") (pin "1") (pinfunction "COM_1") (pintype "bidirectional"))
      (node (ref "SEG2") (pin "11") (pinfunction "COM_11") (pintype "bidirectional"))
      (node (ref "T2") (pin "1") (pinfunction "D_1") (pintype "passive"))
    )
    (net (code "68") (name "ROW2") (class "Default")
      (node (ref "SEG3") (pin "1") (pinfunction "COM_1") (pintype "bidirectional"))
      (node (ref "SEG3") (pin "11") (pinfunction "COM_11") (pintype "bidirectional"))
      (node (ref "T3") (pin "1") (pinfunction "D_1") (pintype "passive"))
    )
    (net (code "69") (name "ROW3") (class "Default")
      (node (ref "SEG4") (pin "1") (pinfunction "COM_1") (pintype "bidirectional"))
      (node (ref "SEG4") (pin "11") (pinfunction "COM_11") (pintype "bidirectional"))
      (node (ref "T4") (pin "1") (pinfunction "D_1") (pintype "passive"))
    )
    (net (code "70") (name "ROW4") (class "Default")
      (node (ref "SEG5") (pin "1") (pinfunction "COM_1") (pintype "bidirectional"))
      (node (ref "SEG5") (pin "11") (pinfunction "COM_11") (pintype "bidirectional"))
      (node (ref "T5") (pin "1") (pinfunction "D_1") (pintype "passive"))
    )
    (net (code "71") (name "RST") (class "Default")
      (node (ref "IC3") (pin "13") (pinfunction "~{RESET}_13") (pintype "bidirectional"))
      (node (ref "IC4") (pin "13") (pinfunction "~{RESET}_13") (pintype "bidirectional"))
      (node (ref "JP1") (pin "5") (pinfunction "5_5") (pintype "bidirectional"))
      (node (ref "R6") (pin "1") (pinfunction "1_1") (pintype "passive"))
    )
    (net (code "72") (name "SDO") (class "Default")
      (node (ref "IC1") (pin "22") (pinfunction "SDO_22") (pintype "bidirectional"))
      (node (ref "IC2") (pin "2") (pinfunction "SDI_2") (pintype "bidirectional"))
    )
    (net (code "73") (name "UCAP") (class "Default")
      (node (ref "C6") (pin "1") (pinfunction "1_1") (pintype "passive"))
      (node (ref "IC3") (pin "6") (pinfunction "UCAP_6") (pintype "bidirectional"))
      (node (ref "IC4") (pin "6") (pinfunction "UCAP_6") (pintype "bidirectional"))
    )
    (net (code "74") (name "USB_D+") (class "Default")
      (node (ref "IC3") (pin "4") (pinfunction "D+_4") (pintype "bidirectional"))
      (node (ref "IC4") (pin "4") (pinfunction "D+_4") (pintype "bidirectional"))
      (node (ref "R4") (pin "2") (pinfunction "2_2") (pintype "passive"))
    )
    (net (code "75") (name "USB_D-") (class "Default")
      (node (ref "IC3") (pin "3") (pinfunction "D-_3") (pintype "bidirectional"))
      (node (ref "IC4") (pin "3") (pinfunction "D-_3") (pintype "bidirectional"))
      (node (ref "R3") (pin "2") (pinfunction "2_2") (pintype "passive"))
    )
    (net (code "76") (name "VCC5V") (class "Default")
      (node (ref "C1") (pin "1") (pinfunction "1_1") (pintype "passive"))
      (node (ref "C2") (pin "1") (pinfunction "1_1") (pintype "passive"))
      (node (ref "C8") (pin "1") (pinfunction "1_1") (pintype "passive"))
      (node (ref "C9") (pin "1") (pinfunction "1_1") (pintype "passive"))
      (node (ref "D1") (pin "C") (pinfunction "C_C") (pintype "passive"))
      (node (ref "D4") (pin "C") (pinfunction "C_C") (pintype "passive"))
      (node (ref "D5") (pin "C") (pinfunction "C_C") (pintype "passive"))
      (node (ref "IC1") (pin "24") (pinfunction "VDD_24") (pintype "bidirectional"))
      (node (ref "IC2") (pin "24") (pinfunction "VDD_24") (pintype "bidirectional"))
      (node (ref "IC3") (pin "14") (pinfunction "VCC_14") (pintype "bidirectional"))
      (node (ref "IC3") (pin "2") (pinfunction "UVCC_2") (pintype "bidirectional"))
      (node (ref "IC3") (pin "34") (pinfunction "VCC_34") (pintype "bidirectional"))
      (node (ref "IC3") (pin "7") (pinfunction "VBUS_7") (pintype "bidirectional"))
      (node (ref "IC4") (pin "14") (pinfunction "VCC_14") (pintype "bidirectional"))
      (node (ref "IC4") (pin "2") (pinfunction "UVCC_2") (pintype "bidirectional"))
      (node (ref "IC4") (pin "34") (pinfunction "VCC_34") (pintype "bidirectional"))
      (node (ref "IC4") (pin "7") (pinfunction "VBUS_7") (pintype "bidirectional"))
      (node (ref "IC5") (pin "2") (pinfunction "VCC_2") (pintype "bidirectional"))
      (node (ref "IC7") (pin "1") (pinfunction "VIN_1") (pintype "bidirectional"))
      (node (ref "J2") (pin "1") (pinfunction "1_1") (pintype "passive"))
      (node (ref "J2") (pin "2") (pinfunction "2_2") (pintype "passive"))
      (node (ref "JP1") (pin "2") (pinfunction "2_2") (pintype "bidirectional"))
      (node (ref "JP3") (pin "1") (pinfunction "1_1") (pintype "passive"))
      (node (ref "JP6") (pin "10") (pinfunction "10_10") (pintype "passive"))
      (node (ref "L1") (pin "1") (pinfunction "1_1") (pintype "passive"))
      (node (ref "R18") (pin "1") (pinfunction "1_1") (pintype "passive"))
      (node (ref "R19") (pin "2") (pinfunction "2_2") (pintype "passive"))
      (node (ref "R6") (pin "2") (pinfunction "2_2") (pintype "passive"))
    )
    (net (code "77") (name "VCC9V") (class "Default")
      (node (ref "C11") (pin "1") (pinfunction "1_1") (pintype "passive"))
      (node (ref "D2") (pin "C") (pinfunction "C_C") (pintype "passive"))
      (node (ref "D3") (pin "C") (pinfunction "C_C") (pintype "passive"))
      (node (ref "IC6") (pin "1") (pinfunction "VI_1") (pintype "input"))
      (node (ref "JP3") (pin "2") (pinfunction "2_2") (pintype "passive"))
      (node (ref "JP6") (pin "9") (pinfunction "9_9") (pintype "passive"))
      (node (ref "R13") (pin "2") (pinfunction "2_2") (pintype "passive"))
      (node (ref "R14") (pin "2") (pinfunction "2_2") (pintype "passive"))
      (node (ref "R15") (pin "2") (pinfunction "2_2") (pintype "passive"))
      (node (ref "R16") (pin "2") (pinfunction "2_2") (pintype "passive"))
      (node (ref "R17") (pin "2") (pinfunction "2_2") (pintype "passive"))
      (node (ref "T1") (pin "2") (pinfunction "S_2") (pintype "passive"))
      (node (ref "T2") (pin "2") (pinfunction "S_2") (pintype "passive"))
      (node (ref "T3") (pin "2") (pinfunction "S_2") (pintype "passive"))
      (node (ref "T4") (pin "2") (pinfunction "S_2") (pintype "passive"))
      (node (ref "T5") (pin "2") (pinfunction "S_2") (pintype "passive"))
    )
    (net (code "78") (name "XTAL1") (class "Default")
      (node (ref "C4") (pin "2") (pinfunction "2_2") (pintype "passive"))
      (node (ref "IC3") (pin "17") (pinfunction "XTAL1_17") (pintype "bidirectional"))
      (node (ref "IC4") (pin "17") (pinfunction "XTAL1_17") (pintype "bidirectional"))
      (node (ref "R5") (pin "2") (pinfunction "2_2") (pintype "passive"))
      (node (ref "X1") (pin "2") (pinfunction "P$2_2") (pintype "bidirectional"))
    )
    (net (code "79") (name "XTAL2") (class "Default")
      (node (ref "C5") (pin "2") (pinfunction "2_2") (pintype "passive"))
      (node (ref "IC3") (pin "16") (pinfunction "XTAL2_16") (pintype "bidirectional"))
      (node (ref "IC4") (pin "16") (pinfunction "XTAL2_16") (pintype "bidirectional"))
      (node (ref "R5") (pin "1") (pinfunction "1_1") (pintype "passive"))
      (node (ref "X1") (pin "1") (pinfunction "P$1_1") (pintype "bidirectional"))
    )
    (net (code "80") (name "unconnected-(CORE-~{RST}-Pad23)") (class "Default")
      (node (ref "CORE") (pin "23") (pinfunction "~{RST}_23") (pintype "bidirectional"))
    )
    (net (code "81") (name "unconnected-(IC1-OUT10-Pad15)") (class "Default")
      (node (ref "IC1") (pin "15") (pinfunction "OUT10_15") (pintype "bidirectional"))
    )
    (net (code "82") (name "unconnected-(IC1-OUT11-Pad16)") (class "Default")
      (node (ref "IC1") (pin "16") (pinfunction "OUT11_16") (pintype "bidirectional"))
    )
    (net (code "83") (name "unconnected-(IC1-OUT12-Pad17)") (class "Default")
      (node (ref "IC1") (pin "17") (pinfunction "OUT12_17") (pintype "bidirectional"))
    )
    (net (code "84") (name "unconnected-(IC1-OUT13-Pad18)") (class "Default")
      (node (ref "IC1") (pin "18") (pinfunction "OUT13_18") (pintype "bidirectional"))
    )
    (net (code "85") (name "unconnected-(IC1-OUT14-Pad19)") (class "Default")
      (node (ref "IC1") (pin "19") (pinfunction "OUT14_19") (pintype "bidirectional"))
    )
    (net (code "86") (name "unconnected-(IC1-OUT15-Pad20)") (class "Default")
      (node (ref "IC1") (pin "20") (pinfunction "OUT15_20") (pintype "bidirectional"))
    )
    (net (code "87") (name "unconnected-(IC2-OUT8-Pad13)") (class "Default")
      (node (ref "IC2") (pin "13") (pinfunction "OUT8_13") (pintype "bidirectional"))
    )
    (net (code "88") (name "unconnected-(IC2-OUT9-Pad14)") (class "Default")
      (node (ref "IC2") (pin "14") (pinfunction "OUT9_14") (pintype "bidirectional"))
    )
    (net (code "89") (name "unconnected-(IC2-OUT10-Pad15)") (class "Default")
      (node (ref "IC2") (pin "15") (pinfunction "OUT10_15") (pintype "bidirectional"))
    )
    (net (code "90") (name "unconnected-(IC2-OUT11-Pad16)") (class "Default")
      (node (ref "IC2") (pin "16") (pinfunction "OUT11_16") (pintype "bidirectional"))
    )
    (net (code "91") (name "unconnected-(IC2-OUT12-Pad17)") (class "Default")
      (node (ref "IC2") (pin "17") (pinfunction "OUT12_17") (pintype "bidirectional"))
    )
    (net (code "92") (name "unconnected-(IC2-OUT13-Pad18)") (class "Default")
      (node (ref "IC2") (pin "18") (pinfunction "OUT13_18") (pintype "bidirectional"))
    )
    (net (code "93") (name "unconnected-(IC2-OUT14-Pad19)") (class "Default")
      (node (ref "IC2") (pin "19") (pinfunction "OUT14_19") (pintype "bidirectional"))
    )
    (net (code "94") (name "unconnected-(IC2-OUT15-Pad20)") (class "Default")
      (node (ref "IC2") (pin "20") (pinfunction "OUT15_20") (pintype "bidirectional"))
    )
    (net (code "95") (name "unconnected-(IC2-SDO-Pad22)") (class "Default")
      (node (ref "IC2") (pin "22") (pinfunction "SDO_22") (pintype "bidirectional"))
    )
    (net (code "96") (name "unconnected-(IC5-32K-Pad6)") (class "Default")
      (node (ref "IC5") (pin "6") (pinfunction "32K_6") (pintype "bidirectional"))
    )
    (net (code "97") (name "unconnected-(IC5-BAT-Pad5)") (class "Default")
      (node (ref "IC5") (pin "5") (pinfunction "BAT_5") (pintype "bidirectional"))
    )
    (net (code "98") (name "unconnected-(IC5-RST-Pad8)") (class "Default")
      (node (ref "IC5") (pin "8") (pinfunction "RST_8") (pintype "bidirectional"))
    )
    (net (code "99") (name "unconnected-(J1-PadGNDBREAK)") (class "Default")
      (node (ref "J1") (pin "GNDBREAK") (pinfunction "GNDBREAK_GNDBREAK") (pintype "bidirectional"))
    )
    (net (code "100") (name "unconnected-(J2-Pad18)") (class "Default")
      (node (ref "J2") (pin "18") (pinfunction "18_18") (pintype "passive"))
    )
  )
)
